# SCH_pi_quad_2023-08-11.net
KiCad netlist of a schematic drawn in EasyEDA
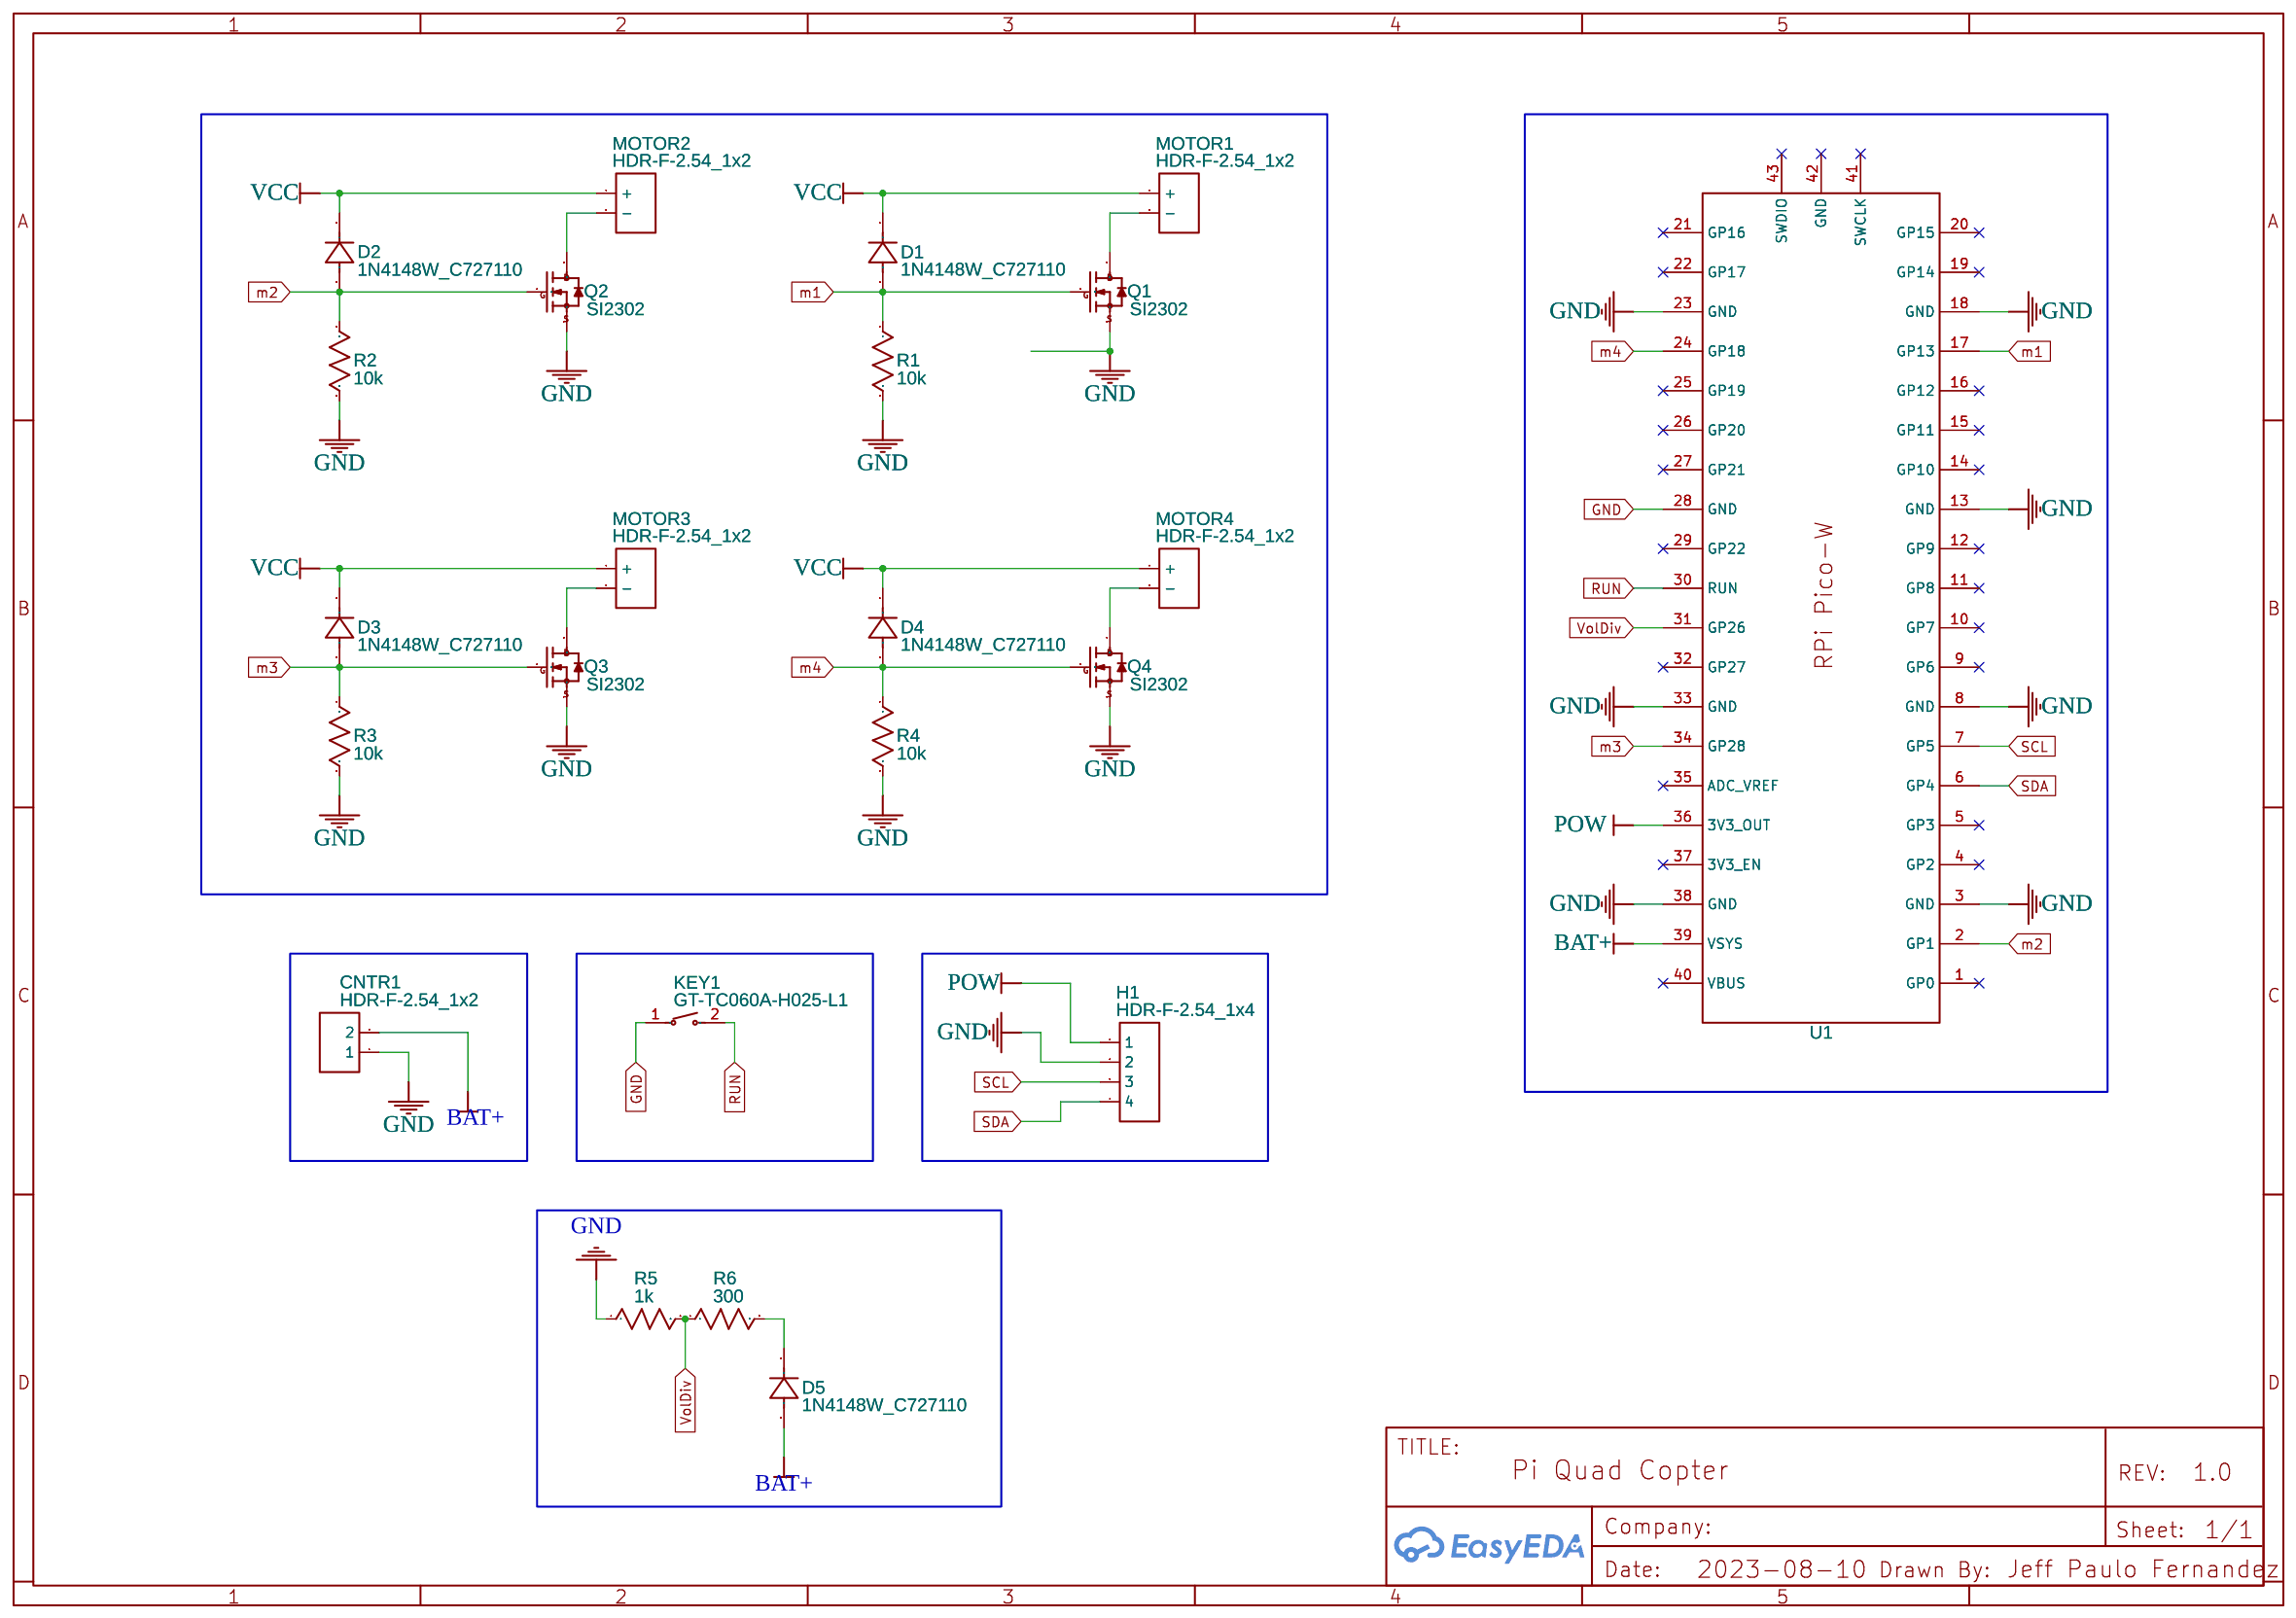
[diagram p0: schematic sheet]

(export (version "E")
  (design (tool "Eeschema 10.0.6"))
  (components
    (comp (ref "CNTR1") (value "HDR-F-2.54_1x2") (libsource (lib "") (part "HDR-F-2.54_1x2_1")))
    (comp (ref "D1")
      (value "1N4148W_C727110")
      (fields (field (name "Manufacturer Part") "1N4148W") (field (name "Manufacturer") "TWGMC(台湾迪嘉)"))
      (libsource (lib "") (part "1N4148W_C727110"))
    )
    (comp (ref "D2")
      (value "1N4148W_C727110")
      (fields (field (name "Manufacturer Part") "1N4148W") (field (name "Manufacturer") "TWGMC(台湾迪嘉)"))
      (libsource (lib "") (part "1N4148W_C727110"))
    )
    (comp (ref "D3")
      (value "1N4148W_C727110")
      (fields (field (name "Manufacturer Part") "1N4148W") (field (name "Manufacturer") "TWGMC(台湾迪嘉)"))
      (libsource (lib "") (part "1N4148W_C727110"))
    )
    (comp (ref "D4")
      (value "1N4148W_C727110")
      (fields (field (name "Manufacturer Part") "1N4148W") (field (name "Manufacturer") "TWGMC(台湾迪嘉)"))
      (libsource (lib "") (part "1N4148W_C727110"))
    )
    (comp (ref "D5")
      (value "1N4148W_C727110")
      (fields (field (name "Manufacturer Part") "1N4148W") (field (name "Manufacturer") "TWGMC(台湾迪嘉)"))
      (libsource (lib "") (part "1N4148W_C727110"))
    )
    (comp (ref "H1") (value "HDR-F-2.54_1x4") (libsource (lib "") (part "HDR-F-2.54_1x4")))
    (comp (ref "KEY1")
      (value "GT-TC060A-H025-L1")
      (fields (field (name "Manufacturer") "G-Switch(品赞)"))
      (libsource (lib "") (part "GT-TC060A-H025-L1"))
    )
    (comp (ref "MOTOR1") (value "HDR-F-2.54_1x2") (libsource (lib "") (part "HDR-F-2.54_1x2")))
    (comp (ref "MOTOR2") (value "HDR-F-2.54_1x2") (libsource (lib "") (part "HDR-F-2.54_1x2")))
    (comp (ref "MOTOR3") (value "HDR-F-2.54_1x2") (libsource (lib "") (part "HDR-F-2.54_1x2")))
    (comp (ref "MOTOR4") (value "HDR-F-2.54_1x2") (libsource (lib "") (part "HDR-F-2.54_1x2")))
    (comp (ref "Q1")
      (value "SI2302")
      (fields (field (name "Manufacturer") "Hottech(合科泰)"))
      (libsource (lib "") (part "SI2302"))
    )
    (comp (ref "Q2")
      (value "SI2302")
      (fields (field (name "Manufacturer") "Hottech(合科泰)"))
      (libsource (lib "") (part "SI2302"))
    )
    (comp (ref "Q3")
      (value "SI2302")
      (fields (field (name "Manufacturer") "Hottech(合科泰)"))
      (libsource (lib "") (part "SI2302"))
    )
    (comp (ref "Q4")
      (value "SI2302")
      (fields (field (name "Manufacturer") "Hottech(合科泰)"))
      (libsource (lib "") (part "SI2302"))
    )
    (comp (ref "R1") (value "10k") (libsource (lib "") (part "R_0603_US")))
    (comp (ref "R2") (value "10k") (libsource (lib "") (part "R_0603_US")))
    (comp (ref "R3") (value "10k") (libsource (lib "") (part "R_0603_US")))
    (comp (ref "R4") (value "10k") (libsource (lib "") (part "R_0603_US")))
    (comp (ref "R5") (value "1k") (libsource (lib "") (part "R_0603_US_1")))
    (comp (ref "R6") (value "300") (libsource (lib "") (part "R_0603_US_1")))
    (comp (ref "U1")
      (value "~")
      (fields
        (field (name "Manufacturer Part") "Pi Pico")
        (field (name "Manufacturer") "Raspberry Pi Foundation")
      )
      (libsource (lib "") (part "RPi Pico-W"))
    )
  )
  (nets
    (net (code "1") (name "BAT+") (class "Default")
      (node (ref "CNTR1") (pin "2") (pinfunction "2_2") (pintype "input"))
      (node (ref "D5") (pin "2") (pinfunction "A_2") (pintype "unspecified"))
      (node (ref "U1") (pin "39") (pinfunction "VSYS_39") (pintype "unspecified"))
    )
    (net (code "2") (name "GND") (class "Default")
      (node (ref "CNTR1") (pin "1") (pinfunction "1_1") (pintype "input"))
      (node (ref "H1") (pin "2") (pinfunction "2_2") (pintype "unspecified"))
      (node (ref "KEY1") (pin "1") (pinfunction "1_1") (pintype "unspecified"))
      (node (ref "Q1") (pin "2") (pinfunction "S_2") (pintype "unspecified"))
      (node (ref "Q2") (pin "2") (pinfunction "S_2") (pintype "unspecified"))
      (node (ref "Q3") (pin "2") (pinfunction "S_2") (pintype "unspecified"))
      (node (ref "Q4") (pin "2") (pinfunction "S_2") (pintype "unspecified"))
      (node (ref "R1") (pin "2") (pinfunction "2_2") (pintype "unspecified"))
      (node (ref "R2") (pin "2") (pinfunction "2_2") (pintype "unspecified"))
      (node (ref "R3") (pin "2") (pinfunction "2_2") (pintype "unspecified"))
      (node (ref "R4") (pin "2") (pinfunction "2_2") (pintype "unspecified"))
      (node (ref "R5") (pin "1") (pinfunction "1_1") (pintype "unspecified"))
      (node (ref "U1") (pin "13") (pinfunction "GND_13") (pintype "unspecified"))
      (node (ref "U1") (pin "18") (pinfunction "GND_18") (pintype "unspecified"))
      (node (ref "U1") (pin "23") (pinfunction "GND_23") (pintype "unspecified"))
      (node (ref "U1") (pin "28") (pinfunction "GND_28") (pintype "unspecified"))
      (node (ref "U1") (pin "3") (pinfunction "GND_3") (pintype "unspecified"))
      (node (ref "U1") (pin "33") (pinfunction "GND_33") (pintype "unspecified"))
      (node (ref "U1") (pin "38") (pinfunction "GND_38") (pintype "unspecified"))
      (node (ref "U1") (pin "8") (pinfunction "GND_8") (pintype "unspecified"))
    )
    (net (code "3") (name "Net-(D5-K)") (class "Default")
      (node (ref "D5") (pin "1") (pinfunction "K_1") (pintype "unspecified"))
      (node (ref "R6") (pin "2") (pinfunction "2_2") (pintype "unspecified"))
    )
    (net (code "4") (name "Net-(MOTOR1--)") (class "Default")
      (node (ref "MOTOR1") (pin "2") (pinfunction "-_2") (pintype "input"))
      (node (ref "Q1") (pin "3") (pinfunction "D_3") (pintype "unspecified"))
    )
    (net (code "5") (name "Net-(MOTOR2--)") (class "Default")
      (node (ref "MOTOR2") (pin "2") (pinfunction "-_2") (pintype "input"))
      (node (ref "Q2") (pin "3") (pinfunction "D_3") (pintype "unspecified"))
    )
    (net (code "6") (name "Net-(MOTOR3--)") (class "Default")
      (node (ref "MOTOR3") (pin "2") (pinfunction "-_2") (pintype "input"))
      (node (ref "Q3") (pin "3") (pinfunction "D_3") (pintype "unspecified"))
    )
    (net (code "7") (name "Net-(MOTOR4--)") (class "Default")
      (node (ref "MOTOR4") (pin "2") (pinfunction "-_2") (pintype "input"))
      (node (ref "Q4") (pin "3") (pinfunction "D_3") (pintype "unspecified"))
    )
    (net (code "8") (name "POW") (class "Default")
      (node (ref "H1") (pin "1") (pinfunction "1_1") (pintype "unspecified"))
      (node (ref "U1") (pin "36") (pinfunction "3V3_OUT_36") (pintype "unspecified"))
    )
    (net (code "9") (name "RUN") (class "Default")
      (node (ref "KEY1") (pin "2") (pinfunction "2_2") (pintype "unspecified"))
      (node (ref "U1") (pin "30") (pinfunction "RUN_30") (pintype "unspecified"))
    )
    (net (code "10") (name "SCL") (class "Default")
      (node (ref "H1") (pin "3") (pinfunction "3_3") (pintype "unspecified"))
      (node (ref "U1") (pin "7") (pinfunction "GP5_7") (pintype "unspecified"))
    )
    (net (code "11") (name "SDA") (class "Default")
      (node (ref "H1") (pin "4") (pinfunction "4_4") (pintype "unspecified"))
      (node (ref "U1") (pin "6") (pinfunction "GP4_6") (pintype "unspecified"))
    )
    (net (code "12") (name "VCC") (class "Default")
      (node (ref "D1") (pin "1") (pinfunction "K_1") (pintype "unspecified"))
      (node (ref "D2") (pin "1") (pinfunction "K_1") (pintype "unspecified"))
      (node (ref "D3") (pin "1") (pinfunction "K_1") (pintype "unspecified"))
      (node (ref "D4") (pin "1") (pinfunction "K_1") (pintype "unspecified"))
      (node (ref "MOTOR1") (pin "1") (pinfunction "+_1") (pintype "input"))
      (node (ref "MOTOR2") (pin "1") (pinfunction "+_1") (pintype "input"))
      (node (ref "MOTOR3") (pin "1") (pinfunction "+_1") (pintype "input"))
      (node (ref "MOTOR4") (pin "1") (pinfunction "+_1") (pintype "input"))
    )
    (net (code "13") (name "VolDiv") (class "Default")
      (node (ref "R5") (pin "2") (pinfunction "2_2") (pintype "unspecified"))
      (node (ref "R6") (pin "1") (pinfunction "1_1") (pintype "unspecified"))
      (node (ref "U1") (pin "31") (pinfunction "GP26_31") (pintype "unspecified"))
    )
    (net (code "14") (name "m1") (class "Default")
      (node (ref "D1") (pin "2") (pinfunction "A_2") (pintype "unspecified"))
      (node (ref "Q1") (pin "1") (pinfunction "G_1") (pintype "unspecified"))
      (node (ref "R1") (pin "1") (pinfunction "1_1") (pintype "unspecified"))
      (node (ref "U1") (pin "17") (pinfunction "GP13_17") (pintype "unspecified"))
    )
    (net (code "15") (name "m2") (class "Default")
      (node (ref "D2") (pin "2") (pinfunction "A_2") (pintype "unspecified"))
      (node (ref "Q2") (pin "1") (pinfunction "G_1") (pintype "unspecified"))
      (node (ref "R2") (pin "1") (pinfunction "1_1") (pintype "unspecified"))
      (node (ref "U1") (pin "2") (pinfunction "GP1_2") (pintype "unspecified"))
    )
    (net (code "16") (name "m3") (class "Default")
      (node (ref "D3") (pin "2") (pinfunction "A_2") (pintype "unspecified"))
      (node (ref "Q3") (pin "1") (pinfunction "G_1") (pintype "unspecified"))
      (node (ref "R3") (pin "1") (pinfunction "1_1") (pintype "unspecified"))
      (node (ref "U1") (pin "34") (pinfunction "GP28_34") (pintype "unspecified"))
    )
    (net (code "17") (name "m4") (class "Default")
      (node (ref "D4") (pin "2") (pinfunction "A_2") (pintype "unspecified"))
      (node (ref "Q4") (pin "1") (pinfunction "G_1") (pintype "unspecified"))
      (node (ref "R4") (pin "1") (pinfunction "1_1") (pintype "unspecified"))
      (node (ref "U1") (pin "24") (pinfunction "GP18_24") (pintype "unspecified"))
    )
    (net (code "18") (name "unconnected-(U1-3V3_EN-Pad37)") (class "Default")
      (node (ref "U1") (pin "37") (pinfunction "3V3_EN_37") (pintype "unspecified+no_connect"))
    )
    (net (code "19") (name "unconnected-(U1-ADC_VREF-Pad35)") (class "Default")
      (node (ref "U1") (pin "35") (pinfunction "ADC_VREF_35") (pintype "unspecified+no_connect"))
    )
    (net (code "20") (name "unconnected-(U1-GND-Pad42)") (class "Default")
      (node (ref "U1") (pin "42") (pinfunction "GND_42") (pintype "unspecified+no_connect"))
    )
    (net (code "21") (name "unconnected-(U1-GP0-Pad1)") (class "Default")
      (node (ref "U1") (pin "1") (pinfunction "GP0_1") (pintype "unspecified+no_connect"))
    )
    (net (code "22") (name "unconnected-(U1-GP2-Pad4)") (class "Default")
      (node (ref "U1") (pin "4") (pinfunction "GP2_4") (pintype "unspecified+no_connect"))
    )
    (net (code "23") (name "unconnected-(U1-GP3-Pad5)") (class "Default")
      (node (ref "U1") (pin "5") (pinfunction "GP3_5") (pintype "unspecified+no_connect"))
    )
    (net (code "24") (name "unconnected-(U1-GP6-Pad9)") (class "Default")
      (node (ref "U1") (pin "9") (pinfunction "GP6_9") (pintype "unspecified+no_connect"))
    )
    (net (code "25") (name "unconnected-(U1-GP7-Pad10)") (class "Default")
      (node (ref "U1") (pin "10") (pinfunction "GP7_10") (pintype "unspecified+no_connect"))
    )
    (net (code "26") (name "unconnected-(U1-GP8-Pad11)") (class "Default")
      (node (ref "U1") (pin "11") (pinfunction "GP8_11") (pintype "unspecified+no_connect"))
    )
    (net (code "27") (name "unconnected-(U1-GP9-Pad12)") (class "Default")
      (node (ref "U1") (pin "12") (pinfunction "GP9_12") (pintype "unspecified+no_connect"))
    )
    (net (code "28") (name "unconnected-(U1-GP10-Pad14)") (class "Default")
      (node (ref "U1") (pin "14") (pinfunction "GP10_14") (pintype "unspecified+no_connect"))
    )
    (net (code "29") (name "unconnected-(U1-GP11-Pad15)") (class "Default")
      (node (ref "U1") (pin "15") (pinfunction "GP11_15") (pintype "unspecified+no_connect"))
    )
    (net (code "30") (name "unconnected-(U1-GP12-Pad16)") (class "Default")
      (node (ref "U1") (pin "16") (pinfunction "GP12_16") (pintype "unspecified+no_connect"))
    )
    (net (code "31") (name "unconnected-(U1-GP14-Pad19)") (class "Default")
      (node (ref "U1") (pin "19") (pinfunction "GP14_19") (pintype "unspecified+no_connect"))
    )
    (net (code "32") (name "unconnected-(U1-GP15-Pad20)") (class "Default")
      (node (ref "U1") (pin "20") (pinfunction "GP15_20") (pintype "unspecified+no_connect"))
    )
    (net (code "33") (name "unconnected-(U1-GP16-Pad21)") (class "Default")
      (node (ref "U1") (pin "21") (pinfunction "GP16_21") (pintype "unspecified+no_connect"))
    )
    (net (code "34") (name "unconnected-(U1-GP17-Pad22)") (class "Default")
      (node (ref "U1") (pin "22") (pinfunction "GP17_22") (pintype "unspecified+no_connect"))
    )
    (net (code "35") (name "unconnected-(U1-GP19-Pad25)") (class "Default")
      (node (ref "U1") (pin "25") (pinfunction "GP19_25") (pintype "unspecified+no_connect"))
    )
    (net (code "36") (name "unconnected-(U1-GP20-Pad26)") (class "Default")
      (node (ref "U1") (pin "26") (pinfunction "GP20_26") (pintype "unspecified+no_connect"))
    )
    (net (code "37") (name "unconnected-(U1-GP21-Pad27)") (class "Default")
      (node (ref "U1") (pin "27") (pinfunction "GP21_27") (pintype "unspecified+no_connect"))
    )
    (net (code "38") (name "unconnected-(U1-GP22-Pad29)") (class "Default")
      (node (ref "U1") (pin "29") (pinfunction "GP22_29") (pintype "unspecified+no_connect"))
    )
    (net (code "39") (name "unconnected-(U1-GP27-Pad32)") (class "Default")
      (node (ref "U1") (pin "32") (pinfunction "GP27_32") (pintype "unspecified+no_connect"))
    )
    (net (code "40") (name "unconnected-(U1-SWCLK-Pad41)") (class "Default")
      (node (ref "U1") (pin "41") (pinfunction "SWCLK_41") (pintype "unspecified+no_connect"))
    )
    (net (code "41") (name "unconnected-(U1-SWDIO-Pad43)") (class "Default")
      (node (ref "U1") (pin "43") (pinfunction "SWDIO_43") (pintype "unspecified+no_connect"))
    )
    (net (code "42") (name "unconnected-(U1-VBUS-Pad40)") (class "Default")
      (node (ref "U1") (pin "40") (pinfunction "VBUS_40") (pintype "unspecified+no_connect"))
    )
  )
)
